# BatteryModule.net
KiCad netlist of a schematic drawn in EAGLE
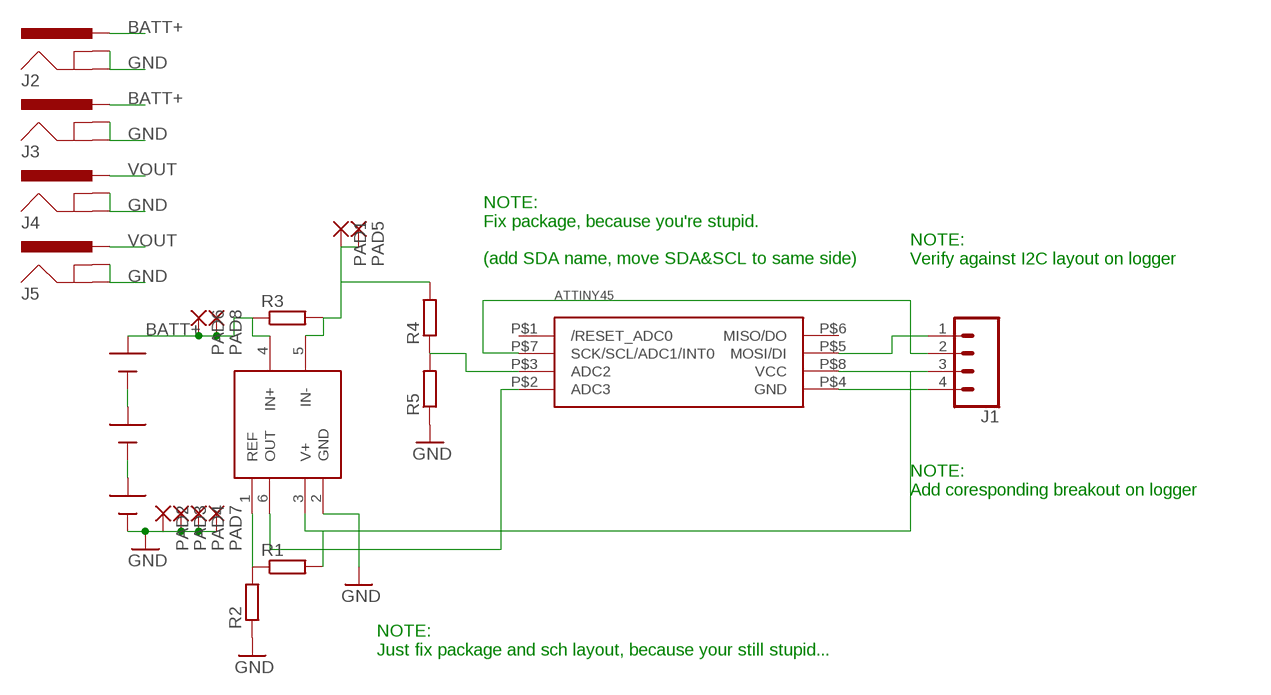
[diagram p0: schematic, sheet 1]

(export (version "E")
  (design (tool "Eeschema 10.0.6"))
  (components
    (comp (ref "J1")
      (value "CONN_04")
      (footprint "eagle-import:1X04")
      (libsource (lib "eagle-import") (part "CONN_04"))
    )
    (comp (ref "J2")
      (value "5.5x2.1mm Barrel")
      (footprint "eagle-import:POWER_JACK_SMD")
      (libsource (lib "eagle-import") (part "POWER_JACKSMD"))
    )
    (comp (ref "J3")
      (value "5.5x2.1mm Barrel")
      (footprint "eagle-import:POWER_JACK_SMD")
      (libsource (lib "eagle-import") (part "POWER_JACKSMD"))
    )
    (comp (ref "J4")
      (value "5.5x2.1mm Barrel")
      (footprint "eagle-import:POWER_JACK_SMD")
      (libsource (lib "eagle-import") (part "POWER_JACKSMD"))
    )
    (comp (ref "J5")
      (value "5.5x2.1mm Barrel")
      (footprint "eagle-import:POWER_JACK_SMD")
      (libsource (lib "eagle-import") (part "POWER_JACKSMD"))
    )
    (comp (ref "PAD1")
      (value "2,15/1,0")
      (footprint "eagle-import:2,15_1,0")
      (libsource (lib "eagle-import") (part "2,15/1,0"))
    )
    (comp (ref "PAD2")
      (value "2,15/1,0")
      (footprint "eagle-import:2,15_1,0")
      (libsource (lib "eagle-import") (part "2,15/1,0"))
    )
    (comp (ref "PAD3")
      (value "2,15/1,0")
      (footprint "eagle-import:2,15_1,0")
      (libsource (lib "eagle-import") (part "2,15/1,0"))
    )
    (comp (ref "PAD4")
      (value "2,15/1,0")
      (footprint "eagle-import:2,15_1,0")
      (libsource (lib "eagle-import") (part "2,15/1,0"))
    )
    (comp (ref "PAD5")
      (value "2,15/1,0")
      (footprint "eagle-import:2,15_1,0")
      (libsource (lib "eagle-import") (part "2,15/1,0"))
    )
    (comp (ref "PAD6")
      (value "2,15/1,0")
      (footprint "eagle-import:2,15_1,0")
      (libsource (lib "eagle-import") (part "2,15/1,0"))
    )
    (comp (ref "PAD7")
      (value "2,15/1,0")
      (footprint "eagle-import:2,15_1,0")
      (libsource (lib "eagle-import") (part "2,15/1,0"))
    )
    (comp (ref "PAD8")
      (value "2,15/1,0")
      (footprint "eagle-import:2,15_1,0")
      (libsource (lib "eagle-import") (part "2,15/1,0"))
    )
    (comp (ref "R1")
      (value "R-EU_R0603")
      (footprint "eagle-import:R0603")
      (libsource (lib "eagle-import") (part "R-EU_R0603"))
    )
    (comp (ref "R2")
      (value "R-EU_R0603")
      (footprint "eagle-import:R0603")
      (libsource (lib "eagle-import") (part "R-EU_R0603"))
    )
    (comp (ref "R3")
      (value "R-EU_R0805")
      (footprint "eagle-import:R0805")
      (libsource (lib "eagle-import") (part "R-EU_R0805"))
    )
    (comp (ref "R4")
      (value "R-EU_R0603")
      (footprint "eagle-import:R0603")
      (libsource (lib "eagle-import") (part "R-EU_R0603"))
    )
    (comp (ref "R5")
      (value "R-EU_R0603")
      (footprint "eagle-import:R0603")
      (libsource (lib "eagle-import") (part "R-EU_R0603"))
    )
    (comp (ref "U$1")
      (value "18650")
      (footprint "eagle-import:BATT_18650_CLIP")
      (libsource (lib "eagle-import") (part "18650"))
    )
    (comp (ref "U$2")
      (value "18650")
      (footprint "eagle-import:BATT_18650_CLIP")
      (libsource (lib "eagle-import") (part "18650"))
    )
    (comp (ref "U$3")
      (value "18650")
      (footprint "eagle-import:BATT_18650_CLIP")
      (libsource (lib "eagle-import") (part "18650"))
    )
    (comp (ref "U$4")
      (value "ATTINY45")
      (footprint "eagle-import:SOIC8")
      (libsource (lib "eagle-import") (part "ATTINY45"))
    )
    (comp (ref "U$5")
      (value "INA212")
      (footprint "eagle-import:TSOT23-6_DDC")
      (libsource (lib "eagle-import") (part "INA212"))
    )
  )
  (nets
    (net (code "1") (name "/BATT+") (class "Default")
      (node (ref "J2") (pin "VIN0") (pinfunction "PWR_VIN0") (pintype "bidirectional"))
      (node (ref "J3") (pin "VIN0") (pinfunction "PWR_VIN0") (pintype "bidirectional"))
      (node (ref "PAD6") (pin "1") (pinfunction "P_1") (pintype "passive"))
      (node (ref "PAD8") (pin "1") (pinfunction "P_1") (pintype "passive"))
      (node (ref "R3") (pin "1") (pinfunction "1_1") (pintype "passive"))
      (node (ref "U$3") (pin "BATT+@1") (pinfunction "BATT+_BATT+@1") (pintype "bidirectional"))
      (node (ref "U$5") (pin "4") (pinfunction "IN+_4") (pintype "bidirectional"))
    )
    (net (code "2") (name "/VOUT") (class "Default")
      (node (ref "J4") (pin "VIN0") (pinfunction "PWR_VIN0") (pintype "bidirectional"))
      (node (ref "J5") (pin "VIN0") (pinfunction "PWR_VIN0") (pintype "bidirectional"))
      (node (ref "PAD1") (pin "1") (pinfunction "P_1") (pintype "passive"))
      (node (ref "PAD5") (pin "1") (pinfunction "P_1") (pintype "passive"))
      (node (ref "R3") (pin "2") (pinfunction "2_2") (pintype "passive"))
      (node (ref "R4") (pin "2") (pinfunction "2_2") (pintype "passive"))
      (node (ref "U$5") (pin "5") (pinfunction "IN-_5") (pintype "bidirectional"))
    )
    (net (code "3") (name "GND") (class "Default")
      (node (ref "J2") (pin "GND") (pinfunction "GNDBREAK_GND") (pintype "bidirectional"))
      (node (ref "J2") (pin "P$4") (pinfunction "GND_P$4") (pintype "bidirectional"))
      (node (ref "J3") (pin "GND") (pinfunction "GNDBREAK_GND") (pintype "bidirectional"))
      (node (ref "J3") (pin "P$4") (pinfunction "GND_P$4") (pintype "bidirectional"))
      (node (ref "J4") (pin "GND") (pinfunction "GNDBREAK_GND") (pintype "bidirectional"))
      (node (ref "J4") (pin "P$4") (pinfunction "GND_P$4") (pintype "bidirectional"))
      (node (ref "J5") (pin "GND") (pinfunction "GNDBREAK_GND") (pintype "bidirectional"))
      (node (ref "J5") (pin "P$4") (pinfunction "GND_P$4") (pintype "bidirectional"))
      (node (ref "PAD2") (pin "1") (pinfunction "P_1") (pintype "passive"))
      (node (ref "PAD3") (pin "1") (pinfunction "P_1") (pintype "passive"))
      (node (ref "PAD4") (pin "1") (pinfunction "P_1") (pintype "passive"))
      (node (ref "PAD7") (pin "1") (pinfunction "P_1") (pintype "passive"))
      (node (ref "R2") (pin "1") (pinfunction "1_1") (pintype "passive"))
      (node (ref "R5") (pin "1") (pinfunction "1_1") (pintype "passive"))
      (node (ref "U$1") (pin "BATT-@1") (pinfunction "BATT-_BATT-@1") (pintype "bidirectional"))
      (node (ref "U$5") (pin "2") (pinfunction "GND_2") (pintype "bidirectional"))
    )
    (net (code "4") (name "Net-(U$1-BATT+)") (class "Default")
      (node (ref "U$1") (pin "BATT+@1") (pinfunction "BATT+_BATT+@1") (pintype "bidirectional"))
      (node (ref "U$2") (pin "BATT-@1") (pinfunction "BATT-_BATT-@1") (pintype "bidirectional"))
    )
    (net (code "5") (name "Net-(U$2-BATT+)") (class "Default")
      (node (ref "U$2") (pin "BATT+@1") (pinfunction "BATT+_BATT+@1") (pintype "bidirectional"))
      (node (ref "U$3") (pin "BATT-@1") (pinfunction "BATT-_BATT-@1") (pintype "bidirectional"))
    )
    (net (code "6") (name "Net-(U$4-ADC2)") (class "Default")
      (node (ref "R4") (pin "1") (pinfunction "1_1") (pintype "passive"))
      (node (ref "R5") (pin "2") (pinfunction "2_2") (pintype "passive"))
      (node (ref "U$4") (pin "P$3") (pinfunction "ADC2_P$3") (pintype "bidirectional"))
    )
    (net (code "7") (name "Net-(U$4-ADC3)") (class "Default")
      (node (ref "U$4") (pin "P$2") (pinfunction "ADC3_P$2") (pintype "bidirectional"))
      (node (ref "U$5") (pin "6") (pinfunction "OUT_6") (pintype "bidirectional"))
    )
    (net (code "8") (name "Net-(U$4-GND)") (class "Default")
      (node (ref "J1") (pin "4") (pinfunction "4_4") (pintype "passive"))
      (node (ref "U$4") (pin "P$4") (pinfunction "GND_P$4") (pintype "bidirectional"))
    )
    (net (code "9") (name "Net-(U$4-MOSI{slash}DI)") (class "Default")
      (node (ref "J1") (pin "1") (pinfunction "1_1") (pintype "passive"))
      (node (ref "U$4") (pin "P$5") (pinfunction "MOSI/DI_P$5") (pintype "bidirectional"))
    )
    (net (code "10") (name "Net-(U$4-SCK{slash}SCL{slash}ADC1{slash}INT0)") (class "Default")
      (node (ref "J1") (pin "2") (pinfunction "2_2") (pintype "passive"))
      (node (ref "U$4") (pin "P$7") (pinfunction "SCK/SCL/ADC1/INT0_P$7") (pintype "bidirectional"))
    )
    (net (code "11") (name "Net-(U$4-VCC)") (class "Default")
      (node (ref "J1") (pin "3") (pinfunction "3_3") (pintype "passive"))
      (node (ref "R1") (pin "2") (pinfunction "2_2") (pintype "passive"))
      (node (ref "U$4") (pin "P$8") (pinfunction "VCC_P$8") (pintype "bidirectional"))
      (node (ref "U$5") (pin "3") (pinfunction "V+_3") (pintype "bidirectional"))
    )
    (net (code "12") (name "Net-(U$5-REF)") (class "Default")
      (node (ref "R1") (pin "1") (pinfunction "1_1") (pintype "passive"))
      (node (ref "R2") (pin "2") (pinfunction "2_2") (pintype "passive"))
      (node (ref "U$5") (pin "1") (pinfunction "REF_1") (pintype "bidirectional"))
    )
    (net (code "13") (name "unconnected-(U$4-MISO{slash}DO-PadP$6)") (class "Default")
      (node (ref "U$4") (pin "P$6") (pinfunction "MISO/DO_P$6") (pintype "bidirectional"))
    )
    (net (code "14") (name "unconnected-(U$4-{slash}RESET_ADC0-PadP$1)") (class "Default")
      (node (ref "U$4") (pin "P$1") (pinfunction "/RESET_ADC0_P$1") (pintype "bidirectional"))
    )
  )
)
